# ADC_Subsystem.net
KiCad netlist of a schematic drawn in Altium Designer
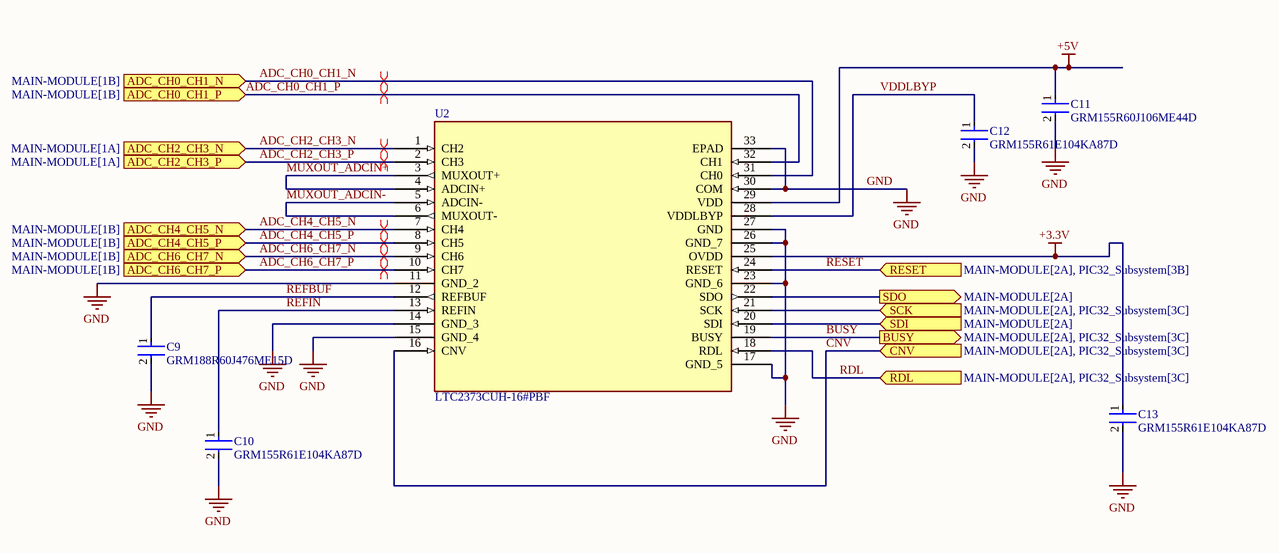
[diagram p0: ADC_Subsystem.SchDoc]

(export (version "E")
  (design (tool "Eeschema 10.0.6"))
  (components
    (comp (ref "C9")
      (value "GRM188R60J476ME15D")
      (footprint "FP-GRM188-0_2-IPC_B")
      (description "Chip Multilayer Ceramic Capacitors for General Purpose, 0603, 47uF, X5R, 15%, 20%, 6.3V")
      (fields (field (name "TOLERANCE") "20%"))
      (libsource (lib "Altium Content Vault") (part "11868f565c42a9108669ba33697ecf6"))
    )
    (comp (ref "C10")
      (value "GRM155R61E104KA87D")
      (footprint "FP-GRM155-0_05-IPC_A")
      (description "CAP CER 0.1UF 25V X5R 0402")
      (fields (field (name "VOLTAGE") "25V") (field (name "TOLERANCE") "10%"))
      (libsource (lib "Altium Content Vault") (part "11868f565c42a9108669ba33697ecf6"))
    )
    (comp (ref "C11")
      (value "GRM155R60J106ME44D")
      (footprint "FP-GRM155-0_2-IPC_A")
      (description "CAP CER 10UF 6.3V X5R 0402")
      (fields (field (name "VOLTAGE") "6.3V") (field (name "TOLERANCE") "20%"))
      (libsource (lib "Altium Content Vault") (part "b4654b650e69147ec39a6b967a45e02"))
    )
    (comp (ref "C12")
      (value "GRM155R61E104KA87D")
      (footprint "FP-GRM155-0_05-IPC_A")
      (description "CAP CER 0.1UF 25V X5R 0402")
      (fields (field (name "VOLTAGE") "25V") (field (name "TOLERANCE") "10%"))
      (libsource (lib "Altium Content Vault") (part "11868f565c42a9108669ba33697ecf6"))
    )
    (comp (ref "C13")
      (value "GRM155R61E104KA87D")
      (footprint "FP-GRM155-0_05-IPC_A")
      (description "CAP CER 0.1UF 25V X5R 0402")
      (fields (field (name "VOLTAGE") "25V") (field (name "TOLERANCE") "10%"))
      (libsource (lib "Altium Content Vault") (part "11868f565c42a9108669ba33697ecf6"))
    )
    (comp (ref "U2")
      (value "LTC2373CUH-16#PBF")
      (footprint "LTC_2373_Footprint")
      (libsource (lib "LTC2373CUH-16#PBF") (part "LTC2373CUH-16#PBF"))
    )
  )
  (nets
    (net (code "1") (name "+3.3V") (class "Default")
      (node (ref "C13") (pin "1") (pinfunction "1_1") (pintype "passive"))
      (node (ref "U2") (pin "25") (pinfunction "OVDD_25") (pintype "power_in"))
    )
    (net (code "2") (name "+5V") (class "Default")
      (node (ref "C11") (pin "1") (pinfunction "1_1") (pintype "passive"))
      (node (ref "U2") (pin "29") (pinfunction "VDD_29") (pintype "power_in"))
    )
    (net (code "3") (name "/ADC_CH0_CH1_N") (class "Default")
      (node (ref "U2") (pin "31") (pinfunction "CH0_31") (pintype "input"))
    )
    (net (code "4") (name "/ADC_CH0_CH1_P") (class "Default")
      (node (ref "U2") (pin "32") (pinfunction "CH1_32") (pintype "input"))
    )
    (net (code "5") (name "/ADC_CH2_CH3_N") (class "Default")
      (node (ref "U2") (pin "1") (pinfunction "CH2_1") (pintype "input"))
    )
    (net (code "6") (name "/ADC_CH2_CH3_P") (class "Default")
      (node (ref "U2") (pin "2") (pinfunction "CH3_2") (pintype "input"))
    )
    (net (code "7") (name "/ADC_CH4_CH5_N") (class "Default")
      (node (ref "U2") (pin "7") (pinfunction "CH4_7") (pintype "input"))
    )
    (net (code "8") (name "/ADC_CH4_CH5_P") (class "Default")
      (node (ref "U2") (pin "8") (pinfunction "CH5_8") (pintype "input"))
    )
    (net (code "9") (name "/ADC_CH6_CH7_N") (class "Default")
      (node (ref "U2") (pin "9") (pinfunction "CH6_9") (pintype "input"))
    )
    (net (code "10") (name "/ADC_CH6_CH7_P") (class "Default")
      (node (ref "U2") (pin "10") (pinfunction "CH7_10") (pintype "input"))
    )
    (net (code "11") (name "/BUSY") (class "Default")
      (node (ref "U2") (pin "19") (pinfunction "BUSY_19") (pintype "passive"))
    )
    (net (code "12") (name "/CNV") (class "Default")
      (node (ref "U2") (pin "16") (pinfunction "CNV_16") (pintype "input"))
    )
    (net (code "13") (name "/MUXOUT_ADCIN+") (class "Default")
      (node (ref "U2") (pin "3") (pinfunction "MUXOUT+_3") (pintype "output"))
      (node (ref "U2") (pin "4") (pinfunction "ADCIN+_4") (pintype "input"))
    )
    (net (code "14") (name "/MUXOUT_ADCIN-") (class "Default")
      (node (ref "U2") (pin "5") (pinfunction "ADCIN-_5") (pintype "input"))
      (node (ref "U2") (pin "6") (pinfunction "MUXOUT-_6") (pintype "output"))
    )
    (net (code "15") (name "/RDL") (class "Default")
      (node (ref "U2") (pin "18") (pinfunction "RDL_18") (pintype "input"))
    )
    (net (code "16") (name "/REFBUF") (class "Default")
      (node (ref "C9") (pin "1") (pinfunction "1_1") (pintype "passive"))
      (node (ref "U2") (pin "12") (pinfunction "REFBUF_12") (pintype "output"))
    )
    (net (code "17") (name "/REFIN") (class "Default")
      (node (ref "C10") (pin "1") (pinfunction "1_1") (pintype "passive"))
      (node (ref "U2") (pin "13") (pinfunction "REFIN_13") (pintype "input"))
    )
    (net (code "18") (name "/RESET") (class "Default")
      (node (ref "U2") (pin "24") (pinfunction "RESET_24") (pintype "input"))
    )
    (net (code "19") (name "/SCK") (class "Default")
      (node (ref "U2") (pin "21") (pinfunction "SCK_21") (pintype "input"))
    )
    (net (code "20") (name "/SDI") (class "Default")
      (node (ref "U2") (pin "20") (pinfunction "SDI_20") (pintype "input"))
    )
    (net (code "21") (name "/SDO") (class "Default")
      (node (ref "U2") (pin "22") (pinfunction "SDO_22") (pintype "output"))
    )
    (net (code "22") (name "/VDDLBYP") (class "Default")
      (node (ref "C12") (pin "1") (pinfunction "1_1") (pintype "passive"))
      (node (ref "U2") (pin "28") (pinfunction "VDDLBYP_28") (pintype "power_in"))
    )
    (net (code "23") (name "GND") (class "Default")
      (node (ref "C10") (pin "2") (pinfunction "2_2") (pintype "passive"))
      (node (ref "C11") (pin "2") (pinfunction "2_2") (pintype "passive"))
      (node (ref "C12") (pin "2") (pinfunction "2_2") (pintype "passive"))
      (node (ref "C13") (pin "2") (pinfunction "2_2") (pintype "passive"))
      (node (ref "C9") (pin "2") (pinfunction "2_2") (pintype "passive"))
      (node (ref "U2") (pin "11") (pinfunction "GND_2_11") (pintype "power_in"))
      (node (ref "U2") (pin "14") (pinfunction "GND_3_14") (pintype "power_in"))
      (node (ref "U2") (pin "15") (pinfunction "GND_4_15") (pintype "power_in"))
      (node (ref "U2") (pin "17") (pinfunction "GND_5_17") (pintype "power_in"))
      (node (ref "U2") (pin "23") (pinfunction "GND_6_23") (pintype "power_in"))
      (node (ref "U2") (pin "26") (pinfunction "GND_7_26") (pintype "power_in"))
      (node (ref "U2") (pin "27") (pinfunction "GND_27") (pintype "power_in"))
      (node (ref "U2") (pin "30") (pinfunction "COM_30") (pintype "input"))
      (node (ref "U2") (pin "33") (pinfunction "EPAD_33") (pintype "passive"))
    )
  )
)
